# POWER.net
KiCad netlist of a schematic drawn in Altium Designer
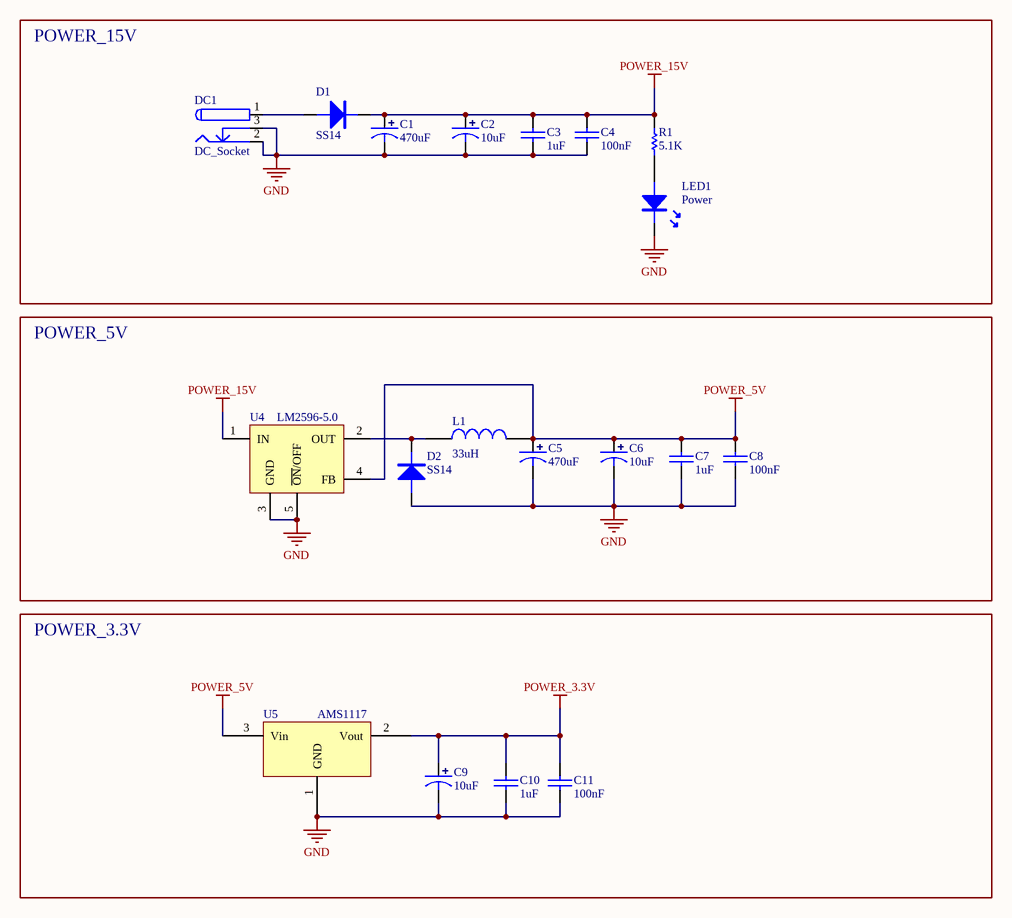
[diagram p0: POWER.SchDoc]

(export (version "E")
  (design (tool "Eeschema 10.0.6"))
  (components
    (comp (ref "C1")
      (value "470uF")
      (footprint "SMD-EC5.0X5.3X5.4")
      (description "贴片电解电容")
      (libsource (lib "电容") (part "SMD_CPOL"))
    )
    (comp (ref "C2")
      (value "10uF")
      (footprint "TAJ-B/3528")
      (description "钽电容")
      (libsource (lib "电容") (part "TCAP_CPOL"))
    )
    (comp (ref "C3")
      (value "1uF")
      (footprint "0603C")
      (description "无极性电容")
      (libsource (lib "电容") (part "CAP"))
    )
    (comp (ref "C4")
      (value "100nF")
      (footprint "0603C")
      (description "无极性电容")
      (libsource (lib "电容") (part "CAP"))
    )
    (comp (ref "C5")
      (value "470uF")
      (footprint "SMD-EC5.0X5.3X5.4")
      (description "贴片电解电容")
      (libsource (lib "电容") (part "SMD_CPOL"))
    )
    (comp (ref "C6")
      (value "10uF")
      (footprint "TAJ-B/3528")
      (description "钽电容")
      (libsource (lib "电容") (part "TCAP_CPOL"))
    )
    (comp (ref "C7")
      (value "1uF")
      (footprint "0603C")
      (description "无极性电容")
      (libsource (lib "电容") (part "CAP"))
    )
    (comp (ref "C8")
      (value "100nF")
      (footprint "0603C")
      (description "无极性电容")
      (libsource (lib "电容") (part "CAP"))
    )
    (comp (ref "C9")
      (value "10uF")
      (footprint "TAJ-B/3528")
      (description "钽电容")
      (libsource (lib "电容") (part "TCAP_CPOL"))
    )
    (comp (ref "C10")
      (value "1uF")
      (footprint "0603C")
      (description "无极性电容")
      (libsource (lib "电容") (part "CAP"))
    )
    (comp (ref "C11")
      (value "100nF")
      (footprint "0603C")
      (description "无极性电容")
      (libsource (lib "电容") (part "CAP"))
    )
    (comp (ref "D1")
      (value "SS14")
      (footprint "SMB/DO-214AA")
      (description "普通二极管")
      (libsource (lib "二极管") (part "DIODE"))
    )
    (comp (ref "D2")
      (value "SS14")
      (footprint "SMB/DO-214AA")
      (description "普通二极管")
      (libsource (lib "二极管") (part "DIODE"))
    )
    (comp (ref "DC1") (value "DC_Socket") (footprint "DC-005") (libsource (lib "电源插座") (part "DC_Socket")))
    (comp (ref "L1")
      (value "33uH")
      (footprint "CDRH74")
      (description "INDUCTOR")
      (libsource (lib "电感") (part "INDUCTOR"))
    )
    (comp (ref "LED1") (value "Power") (footprint "LED-0805R") (libsource (lib "LED") (part "LED")))
    (comp (ref "R1") (value "5.1K") (footprint "0603R") (libsource (lib "电阻") (part "RES")))
    (comp (ref "U4")
      (value "LM2596-5.0")
      (footprint "TO263-5A")
      (description "DC降压芯片")
      (libsource (lib "电源芯片") (part "LM2596-5.0"))
    )
    (comp (ref "U5")
      (value "AMS1117")
      (footprint "SOT223")
      (description "三端稳压芯片")
      (libsource (lib "电源芯片") (part "AMS1117"))
    )
  )
  (nets
    (net (code "1") (name "GND") (class "Default")
      (node (ref "C1") (pin "2") (pinfunction "2_2") (pintype "passive"))
      (node (ref "C10") (pin "1") (pinfunction "1_1") (pintype "passive"))
      (node (ref "C11") (pin "1") (pinfunction "1_1") (pintype "passive"))
      (node (ref "C2") (pin "2") (pinfunction "2_2") (pintype "passive"))
      (node (ref "C3") (pin "1") (pinfunction "1_1") (pintype "passive"))
      (node (ref "C4") (pin "1") (pinfunction "1_1") (pintype "passive"))
      (node (ref "C5") (pin "2") (pinfunction "2_2") (pintype "passive"))
      (node (ref "C6") (pin "2") (pinfunction "2_2") (pintype "passive"))
      (node (ref "C7") (pin "1") (pinfunction "1_1") (pintype "passive"))
      (node (ref "C8") (pin "1") (pinfunction "1_1") (pintype "passive"))
      (node (ref "C9") (pin "2") (pinfunction "2_2") (pintype "passive"))
      (node (ref "D2") (pin "A") (pinfunction "A_A") (pintype "passive"))
      (node (ref "DC1") (pin "2") (pinfunction "2_2") (pintype "power_in"))
      (node (ref "DC1") (pin "3") (pinfunction "3_3") (pintype "power_in"))
      (node (ref "LED1") (pin "K") (pinfunction "K_K") (pintype "passive"))
      (node (ref "U4") (pin "3") (pinfunction "GND_3") (pintype "power_in"))
      (node (ref "U4") (pin "5") (pinfunction "~{ON}/OFF_5") (pintype "passive"))
      (node (ref "U5") (pin "1") (pinfunction "GND_1") (pintype "passive"))
    )
    (net (code "2") (name "Net-(D1-PadA)") (class "Default")
      (node (ref "D1") (pin "A") (pinfunction "A_A") (pintype "passive"))
      (node (ref "DC1") (pin "1") (pinfunction "1_1") (pintype "power_in"))
    )
    (net (code "3") (name "Net-(LED1-PadA)") (class "Default")
      (node (ref "LED1") (pin "A") (pinfunction "A_A") (pintype "passive"))
      (node (ref "R1") (pin "1") (pinfunction "1_1") (pintype "passive"))
    )
    (net (code "4") (name "Net-(U4-OUT)") (class "Default")
      (node (ref "D2") (pin "K") (pinfunction "K_K") (pintype "passive"))
      (node (ref "L1") (pin "1") (pinfunction "1_1") (pintype "passive"))
      (node (ref "U4") (pin "2") (pinfunction "OUT_2") (pintype "power_in"))
    )
    (net (code "5") (name "POWER_3.3V") (class "Default")
      (node (ref "C10") (pin "2") (pinfunction "2_2") (pintype "passive"))
      (node (ref "C11") (pin "2") (pinfunction "2_2") (pintype "passive"))
      (node (ref "C9") (pin "1") (pinfunction "1_1") (pintype "passive"))
      (node (ref "U5") (pin "2") (pinfunction "Vout_2") (pintype "passive"))
    )
    (net (code "6") (name "POWER_5V") (class "Default")
      (node (ref "C5") (pin "1") (pinfunction "1_1") (pintype "passive"))
      (node (ref "C6") (pin "1") (pinfunction "1_1") (pintype "passive"))
      (node (ref "C7") (pin "2") (pinfunction "2_2") (pintype "passive"))
      (node (ref "C8") (pin "2") (pinfunction "2_2") (pintype "passive"))
      (node (ref "L1") (pin "2") (pinfunction "2_2") (pintype "passive"))
      (node (ref "U4") (pin "4") (pinfunction "FB_4") (pintype "passive"))
      (node (ref "U5") (pin "3") (pinfunction "Vin_3") (pintype "passive"))
    )
    (net (code "7") (name "POWER_15V") (class "Default")
      (node (ref "C1") (pin "1") (pinfunction "1_1") (pintype "passive"))
      (node (ref "C2") (pin "1") (pinfunction "1_1") (pintype "passive"))
      (node (ref "C3") (pin "2") (pinfunction "2_2") (pintype "passive"))
      (node (ref "C4") (pin "2") (pinfunction "2_2") (pintype "passive"))
      (node (ref "D1") (pin "K") (pinfunction "K_K") (pintype "passive"))
      (node (ref "R1") (pin "2") (pinfunction "2_2") (pintype "passive"))
      (node (ref "U4") (pin "1") (pinfunction "IN_1") (pintype "power_in"))
    )
  )
)
